# Touch_Cat_0_3.net
KiCad netlist of a schematic drawn in EAGLE
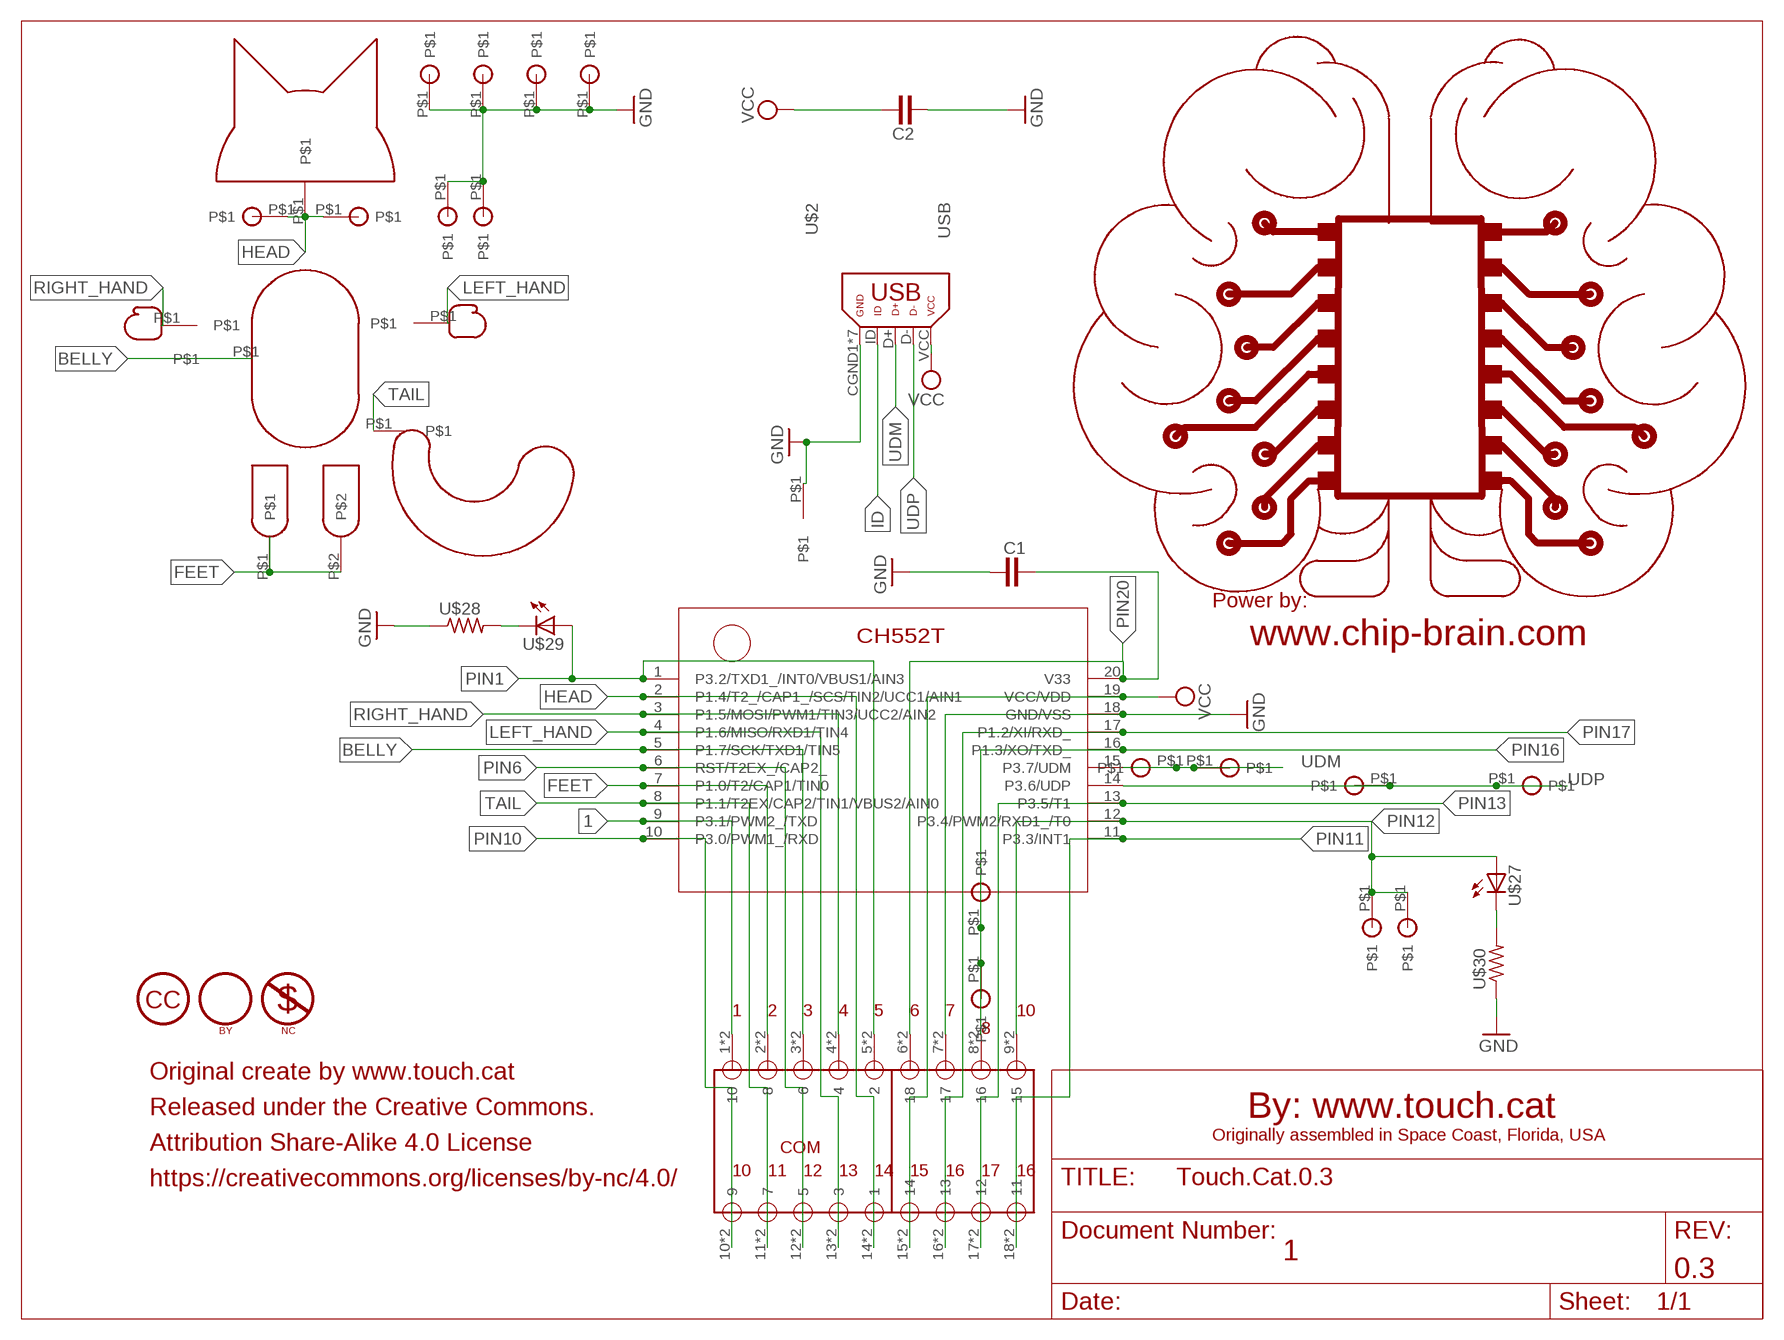
[diagram p0: schematic, sheet 1]

(export (version "E")
  (design (tool "Eeschema 10.0.6"))
  (components
    (comp (ref "C1")
      (value "CAPACITOR")
      (footprint "eagle-import:C0402")
      (libsource (lib "eagle-import") (part "CAPACITOR"))
    )
    (comp (ref "C2")
      (value "CAPACITOR")
      (footprint "eagle-import:C0402")
      (libsource (lib "eagle-import") (part "CAPACITOR"))
    )
    (comp (ref "U$1")
      (value "CHIP-TOUCH-CAT")
      (footprint "eagle-import:TSSOP20")
      (libsource (lib "eagle-import") (part "CHIP-TOUCH-CAT"))
    )
    (comp (ref "U$2")
      (value "USB")
      (footprint "eagle-import:GHI-CONNECTORS_10118192-0001LF(MICRO-USB-B-AMPHENOL-FCI)")
      (libsource (lib "eagle-import") (part "USB"))
    )
    (comp (ref "U$3")
      (value "PADVIA")
      (footprint "eagle-import:PADVIA")
      (libsource (lib "eagle-import") (part "PADVIA"))
    )
    (comp (ref "U$4")
      (value "COM-TOUCH-CAT")
      (footprint "eagle-import:COM")
      (libsource (lib "eagle-import") (part "COM-TOUCH-CAT"))
    )
    (comp (ref "U$5")
      (value "PADVIA")
      (footprint "eagle-import:PADVIA")
      (libsource (lib "eagle-import") (part "PADVIA"))
    )
    (comp (ref "U$6")
      (value "PADVIA")
      (footprint "eagle-import:PADVIA")
      (libsource (lib "eagle-import") (part "PADVIA"))
    )
    (comp (ref "U$7")
      (value "PADVIA")
      (footprint "eagle-import:PADVIA")
      (libsource (lib "eagle-import") (part "PADVIA"))
    )
    (comp (ref "U$8")
      (value "PADVIA")
      (footprint "eagle-import:PADVIA")
      (libsource (lib "eagle-import") (part "PADVIA"))
    )
    (comp (ref "U$9")
      (value "PADVIA")
      (footprint "eagle-import:PADVIA")
      (libsource (lib "eagle-import") (part "PADVIA"))
    )
    (comp (ref "U$11")
      (value "PADVIA")
      (footprint "eagle-import:PADVIA")
      (libsource (lib "eagle-import") (part "PADVIA"))
    )
    (comp (ref "U$12")
      (value "PADVIA")
      (footprint "eagle-import:PADVIA")
      (libsource (lib "eagle-import") (part "PADVIA"))
    )
    (comp (ref "U$13")
      (value "PADVIA")
      (footprint "eagle-import:PADVIA")
      (libsource (lib "eagle-import") (part "PADVIA"))
    )
    (comp (ref "U$14")
      (value "PADVIA")
      (footprint "eagle-import:PADVIA")
      (libsource (lib "eagle-import") (part "PADVIA"))
    )
    (comp (ref "U$15")
      (value "PADVIA")
      (footprint "eagle-import:PADVIA")
      (libsource (lib "eagle-import") (part "PADVIA"))
    )
    (comp (ref "U$16")
      (value "PADVIA")
      (footprint "eagle-import:PADVIA")
      (libsource (lib "eagle-import") (part "PADVIA"))
    )
    (comp (ref "U$17")
      (value "HEAD-TOUCH-CAT")
      (footprint "eagle-import:HEAD-TOUCH-CAT")
      (libsource (lib "eagle-import") (part "HEAD-TOUCH-CAT"))
    )
    (comp (ref "U$18")
      (value "BELLY-TOUCH-CAT")
      (footprint "eagle-import:BELLY-TOUCH-CAT")
      (libsource (lib "eagle-import") (part "BELLY-TOUCH-CAT"))
    )
    (comp (ref "U$19")
      (value "RIGHT_HAND-TOUCH-CAT")
      (footprint "eagle-import:RIGHT_HAND-TOUCH-CAT")
      (libsource (lib "eagle-import") (part "RIGHT_HAND-TOUCH-CAT"))
    )
    (comp (ref "U$20")
      (value "LEFT_HAND-TOUCH-CAT")
      (footprint "eagle-import:LEFT_HAND-TOUCH-CAT")
      (libsource (lib "eagle-import") (part "LEFT_HAND-TOUCH-CAT"))
    )
    (comp (ref "U$21")
      (value "FEET-TOUCH-CAT")
      (footprint "eagle-import:FEET-TOUCH-CAT")
      (libsource (lib "eagle-import") (part "FEET-TOUCH-CAT"))
    )
    (comp (ref "U$22")
      (value "TAIL-TOUCH-CAT")
      (footprint "eagle-import:TAIL-TOUCH-CAT")
      (libsource (lib "eagle-import") (part "TAIL-TOUCH-CAT"))
    )
    (comp (ref "U$23")
      (value "PADVIA")
      (footprint "eagle-import:PADVIA")
      (libsource (lib "eagle-import") (part "PADVIA"))
    )
    (comp (ref "U$24")
      (value "PADVIA")
      (footprint "eagle-import:PADVIA")
      (libsource (lib "eagle-import") (part "PADVIA"))
    )
    (comp (ref "U$25")
      (value "PADVIA")
      (footprint "eagle-import:PADVIA")
      (libsource (lib "eagle-import") (part "PADVIA"))
    )
    (comp (ref "U$26")
      (value "PADVIA")
      (footprint "eagle-import:PADVIA")
      (libsource (lib "eagle-import") (part "PADVIA"))
    )
    (comp (ref "U$27")
      (value "LED-TOUCH-CAT")
      (footprint "eagle-import:0603-ORANGE")
      (libsource (lib "eagle-import") (part "LED-TOUCH-CAT"))
    )
    (comp (ref "U$28")
      (value "RESISTOR-TOUCH-CAT")
      (footprint "eagle-import:R0402")
      (libsource (lib "eagle-import") (part "RESISTOR-TOUCH-CAT"))
    )
    (comp (ref "U$29")
      (value "LED-TOUCH-CAT")
      (footprint "eagle-import:0603-ORANGE")
      (libsource (lib "eagle-import") (part "LED-TOUCH-CAT"))
    )
    (comp (ref "U$30")
      (value "RESISTOR-TOUCH-CAT")
      (footprint "eagle-import:R0402")
      (libsource (lib "eagle-import") (part "RESISTOR-TOUCH-CAT"))
    )
    (comp (ref "U$31")
      (value "OSHW-LOGO")
      (footprint "eagle-import:OSHW-LOGO-MINI")
      (libsource (lib "eagle-import") (part "OSHW-LOGO"))
    )
    (comp (ref "U$32")
      (value "CHIP-BRAIN")
      (footprint "eagle-import:CHIP-BRAIN")
      (libsource (lib "eagle-import") (part "CHIP-BRAIN"))
    )
  )
  (nets
    (net (code "1") (name "1") (class "Default")
      (node (ref "U$1") (pin "9") (pinfunction "P3.1/PWM2_/TXD_9") (pintype "bidirectional"))
      (node (ref "U$4") (pin "1") (pinfunction "10_1") (pintype "bidirectional"))
      (node (ref "U$4") (pin "1.1") (pinfunction "10_1.1") (pintype "bidirectional"))
    )
    (net (code "2") (name "BELLY") (class "Default")
      (node (ref "U$1") (pin "5") (pinfunction "P1.7/SCK/TXD1/TIN5_5") (pintype "bidirectional"))
      (node (ref "U$18") (pin "P$1") (pinfunction "P$1_P$1") (pintype "bidirectional"))
      (node (ref "U$4") (pin "3") (pinfunction "6_3") (pintype "bidirectional"))
      (node (ref "U$4") (pin "3.1") (pinfunction "6_3.1") (pintype "bidirectional"))
    )
    (net (code "3") (name "FEET") (class "Default")
      (node (ref "U$1") (pin "7") (pinfunction "P1.0/T2/CAP1/TIN0_7") (pintype "bidirectional"))
      (node (ref "U$21") (pin "P$1") (pinfunction "P$1_P$1") (pintype "bidirectional"))
      (node (ref "U$21") (pin "P$2") (pinfunction "P$2_P$2") (pintype "bidirectional"))
      (node (ref "U$4") (pin "2") (pinfunction "8_2") (pintype "bidirectional"))
      (node (ref "U$4") (pin "2.1") (pinfunction "8_2.1") (pintype "bidirectional"))
    )
    (net (code "4") (name "GND") (class "Default")
      (node (ref "C1") (pin "1") (pinfunction "1_1") (pintype "passive"))
      (node (ref "C2") (pin "1") (pinfunction "1_1") (pintype "passive"))
      (node (ref "U$1") (pin "18") (pinfunction "GND/VSS_18") (pintype "power_in"))
      (node (ref "U$2") (pin "CGND1") (pinfunction "GND_CGND1") (pintype "passive"))
      (node (ref "U$2") (pin "CGND2") (pinfunction "GND_CGND2") (pintype "passive"))
      (node (ref "U$2") (pin "CGND3") (pinfunction "GND_CGND3") (pintype "passive"))
      (node (ref "U$2") (pin "CGND4") (pinfunction "GND_CGND4") (pintype "passive"))
      (node (ref "U$2") (pin "CGND5") (pinfunction "GND_CGND5") (pintype "passive"))
      (node (ref "U$2") (pin "CGND6") (pinfunction "GND_CGND6") (pintype "passive"))
      (node (ref "U$2") (pin "GND") (pinfunction "GND_GND") (pintype "passive"))
      (node (ref "U$23") (pin "P$1") (pinfunction "P$1_P$1") (pintype "bidirectional"))
      (node (ref "U$24") (pin "P$1") (pinfunction "P$1_P$1") (pintype "bidirectional"))
      (node (ref "U$25") (pin "P$1") (pinfunction "P$1_P$1") (pintype "bidirectional"))
      (node (ref "U$26") (pin "P$1") (pinfunction "P$1_P$1") (pintype "bidirectional"))
      (node (ref "U$28") (pin "1") (pinfunction "1_1") (pintype "passive"))
      (node (ref "U$30") (pin "1") (pinfunction "1_1") (pintype "passive"))
      (node (ref "U$31") (pin "P$1") (pinfunction "P$1_P$1") (pintype "bidirectional"))
      (node (ref "U$4") (pin "7") (pinfunction "17_7") (pintype "bidirectional"))
      (node (ref "U$4") (pin "7.1") (pinfunction "17_7.1") (pintype "bidirectional"))
      (node (ref "U$6") (pin "P$1") (pinfunction "P$1_P$1") (pintype "bidirectional"))
      (node (ref "U$7") (pin "P$1") (pinfunction "P$1_P$1") (pintype "bidirectional"))
    )
    (net (code "5") (name "HEAD") (class "Default")
      (node (ref "U$1") (pin "2") (pinfunction "P1.4/T2_/CAP1_/SCS/TIN2/UCC1/AIN1_2") (pintype "bidirectional"))
      (node (ref "U$17") (pin "P$1") (pinfunction "P$1_P$1") (pintype "bidirectional"))
      (node (ref "U$4") (pin "14") (pinfunction "1_14") (pintype "bidirectional"))
      (node (ref "U$4") (pin "14.1") (pinfunction "1_14.1") (pintype "bidirectional"))
      (node (ref "U$8") (pin "P$1") (pinfunction "P$1_P$1") (pintype "bidirectional"))
      (node (ref "U$9") (pin "P$1") (pinfunction "P$1_P$1") (pintype "bidirectional"))
    )
    (net (code "6") (name "ID") (class "Default")
      (node (ref "U$2") (pin "ID") (pinfunction "ID_ID") (pintype "passive"))
    )
    (net (code "7") (name "LEFT_HAND") (class "Default")
      (node (ref "U$1") (pin "4") (pinfunction "P1.6/MISO/RXD1/TIN4_4") (pintype "bidirectional"))
      (node (ref "U$20") (pin "P$1") (pinfunction "P$1_P$1") (pintype "bidirectional"))
      (node (ref "U$4") (pin "13") (pinfunction "3_13") (pintype "bidirectional"))
      (node (ref "U$4") (pin "13.1") (pinfunction "3_13.1") (pintype "bidirectional"))
    )
    (net (code "8") (name "Net-(U$27-PadC)") (class "Default")
      (node (ref "U$27") (pin "C") (pinfunction "C_C") (pintype "passive"))
      (node (ref "U$30") (pin "2") (pinfunction "2_2") (pintype "passive"))
    )
    (net (code "9") (name "Net-(U$28-Pad2)") (class "Default")
      (node (ref "U$28") (pin "2") (pinfunction "2_2") (pintype "passive"))
      (node (ref "U$29") (pin "C") (pinfunction "C_C") (pintype "passive"))
    )
    (net (code "10") (name "PIN1") (class "Default")
      (node (ref "U$1") (pin "1") (pinfunction "P3.2/TXD1_/INT0/VBUS1/AIN3_1") (pintype "bidirectional"))
      (node (ref "U$29") (pin "A") (pinfunction "A_A") (pintype "passive"))
      (node (ref "U$4") (pin "5") (pinfunction "2_5") (pintype "bidirectional"))
      (node (ref "U$4") (pin "5.1") (pinfunction "2_5.1") (pintype "bidirectional"))
    )
    (net (code "11") (name "PIN6") (class "Default")
      (node (ref "U$1") (pin "6") (pinfunction "RST/T2EX_/CAP2__6") (pintype "bidirectional"))
      (node (ref "U$4") (pin "12") (pinfunction "5_12") (pintype "bidirectional"))
      (node (ref "U$4") (pin "12.1") (pinfunction "5_12.1") (pintype "bidirectional"))
    )
    (net (code "12") (name "PIN10") (class "Default")
      (node (ref "U$1") (pin "10") (pinfunction "P3.0/PWM1_/RXD_10") (pintype "bidirectional"))
      (node (ref "U$4") (pin "10") (pinfunction "9_10") (pintype "bidirectional"))
      (node (ref "U$4") (pin "10.1") (pinfunction "9_10.1") (pintype "bidirectional"))
    )
    (net (code "13") (name "PIN11") (class "Default")
      (node (ref "U$1") (pin "11") (pinfunction "P3.3/INT1_11") (pintype "bidirectional"))
      (node (ref "U$4") (pin "18") (pinfunction "11_18") (pintype "bidirectional"))
      (node (ref "U$4") (pin "18.1") (pinfunction "11_18.1") (pintype "bidirectional"))
    )
    (net (code "14") (name "PIN12") (class "Default")
      (node (ref "U$1") (pin "12") (pinfunction "P3.4/PWM2/RXD1_/T0_12") (pintype "bidirectional"))
      (node (ref "U$27") (pin "A") (pinfunction "A_A") (pintype "passive"))
      (node (ref "U$3") (pin "P$1") (pinfunction "P$1_P$1") (pintype "bidirectional"))
      (node (ref "U$4") (pin "9") (pinfunction "15_9") (pintype "bidirectional"))
      (node (ref "U$4") (pin "9.1") (pinfunction "15_9.1") (pintype "bidirectional"))
      (node (ref "U$5") (pin "P$1") (pinfunction "P$1_P$1") (pintype "bidirectional"))
    )
    (net (code "15") (name "PIN13") (class "Default")
      (node (ref "U$1") (pin "13") (pinfunction "P3.5/T1_13") (pintype "bidirectional"))
      (node (ref "U$4") (pin "17") (pinfunction "12_17") (pintype "bidirectional"))
      (node (ref "U$4") (pin "17.1") (pinfunction "12_17.1") (pintype "bidirectional"))
    )
    (net (code "16") (name "PIN16") (class "Default")
      (node (ref "U$1") (pin "16") (pinfunction "P1.3/XO/TXD__16") (pintype "bidirectional"))
      (node (ref "U$11") (pin "P$1") (pinfunction "P$1_P$1") (pintype "bidirectional"))
      (node (ref "U$12") (pin "P$1") (pinfunction "P$1_P$1") (pintype "bidirectional"))
      (node (ref "U$4") (pin "8") (pinfunction "16_8") (pintype "bidirectional"))
      (node (ref "U$4") (pin "8.1") (pinfunction "16_8.1") (pintype "bidirectional"))
    )
    (net (code "17") (name "PIN17") (class "Default")
      (node (ref "U$1") (pin "17") (pinfunction "P1.2/XI/RXD__17") (pintype "bidirectional"))
      (node (ref "U$4") (pin "16") (pinfunction "13_16") (pintype "bidirectional"))
      (node (ref "U$4") (pin "16.1") (pinfunction "13_16.1") (pintype "bidirectional"))
    )
    (net (code "18") (name "PIN20") (class "Default")
      (node (ref "C1") (pin "2") (pinfunction "2_2") (pintype "passive"))
      (node (ref "U$1") (pin "20") (pinfunction "V33_20") (pintype "power_in"))
      (node (ref "U$4") (pin "6") (pinfunction "18_6") (pintype "bidirectional"))
      (node (ref "U$4") (pin "6.1") (pinfunction "18_6.1") (pintype "bidirectional"))
    )
    (net (code "19") (name "RIGHT_HAND") (class "Default")
      (node (ref "U$1") (pin "3") (pinfunction "P1.5/MOSI/PWM1/TIN3/UCC2/AIN2_3") (pintype "bidirectional"))
      (node (ref "U$19") (pin "P$1") (pinfunction "P$1_P$1") (pintype "bidirectional"))
      (node (ref "U$4") (pin "4") (pinfunction "4_4") (pintype "bidirectional"))
      (node (ref "U$4") (pin "4.1") (pinfunction "4_4.1") (pintype "bidirectional"))
    )
    (net (code "20") (name "TAIL") (class "Default")
      (node (ref "U$1") (pin "8") (pinfunction "P1.1/T2EX/CAP2/TIN1/VBUS2/AIN0_8") (pintype "bidirectional"))
      (node (ref "U$22") (pin "P$1") (pinfunction "P$1_P$1") (pintype "bidirectional"))
      (node (ref "U$4") (pin "11") (pinfunction "7_11") (pintype "bidirectional"))
      (node (ref "U$4") (pin "11.1") (pinfunction "7_11.1") (pintype "bidirectional"))
    )
    (net (code "21") (name "UDM") (class "Default")
      (node (ref "U$1") (pin "15") (pinfunction "P3.7/UDM_15") (pintype "bidirectional"))
      (node (ref "U$13") (pin "P$1") (pinfunction "P$1_P$1") (pintype "bidirectional"))
      (node (ref "U$14") (pin "P$1") (pinfunction "P$1_P$1") (pintype "bidirectional"))
      (node (ref "U$2") (pin "D+") (pinfunction "D+_D+") (pintype "passive"))
    )
    (net (code "22") (name "UDP") (class "Default")
      (node (ref "U$1") (pin "14") (pinfunction "P3.6/UDP_14") (pintype "bidirectional"))
      (node (ref "U$15") (pin "P$1") (pinfunction "P$1_P$1") (pintype "bidirectional"))
      (node (ref "U$16") (pin "P$1") (pinfunction "P$1_P$1") (pintype "bidirectional"))
      (node (ref "U$2") (pin "D-") (pinfunction "D-_D-") (pintype "passive"))
    )
    (net (code "23") (name "VCC") (class "Default")
      (node (ref "C2") (pin "2") (pinfunction "2_2") (pintype "passive"))
      (node (ref "U$1") (pin "19") (pinfunction "VCC/VDD_19") (pintype "power_in"))
      (node (ref "U$2") (pin "VCC") (pinfunction "VCC_VCC") (pintype "passive"))
      (node (ref "U$4") (pin "15") (pinfunction "14_15") (pintype "bidirectional"))
      (node (ref "U$4") (pin "15.1") (pinfunction "14_15.1") (pintype "bidirectional"))
    )
  )
)
